# untitled.net
KiCad netlist of a schematic drawn in EAGLE
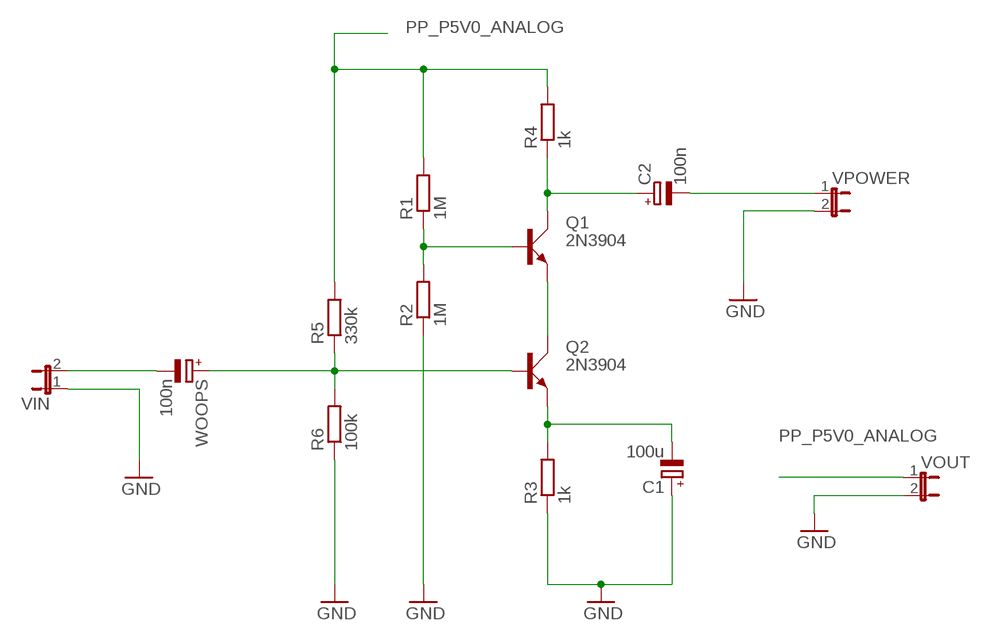
[diagram p0: schematic, sheet 1]

(export (version "E")
  (design (tool "Eeschema 10.0.6"))
  (components
    (comp (ref "C1")
      (value "100u")
      (footprint "eagle-import:E5-10,5")
      (libsource (lib "eagle-import") (part "CPOL-EUE5-10.5"))
    )
    (comp (ref "C2")
      (value "100n")
      (footprint "eagle-import:EB25D")
      (libsource (lib "eagle-import") (part "CPOL-EUE10-25"))
    )
    (comp (ref "Q1")
      (value "2N3904")
      (footprint "eagle-import:TO92D")
      (libsource (lib "eagle-import") (part "2N3904"))
    )
    (comp (ref "Q2")
      (value "2N3904")
      (footprint "eagle-import:TO92D")
      (libsource (lib "eagle-import") (part "2N3904"))
    )
    (comp (ref "R1")
      (value "1M")
      (footprint "eagle-import:0207_10")
      (libsource (lib "eagle-import") (part "R-EU_0207/10"))
    )
    (comp (ref "R2")
      (value "1M")
      (footprint "eagle-import:0207_10")
      (libsource (lib "eagle-import") (part "R-EU_0207/10"))
    )
    (comp (ref "R3")
      (value "1k")
      (footprint "eagle-import:0207_10")
      (libsource (lib "eagle-import") (part "R-EU_0207/10"))
    )
    (comp (ref "R4")
      (value "1k")
      (footprint "eagle-import:0207_10")
      (libsource (lib "eagle-import") (part "R-EU_0207/10"))
    )
    (comp (ref "R5")
      (value "330k")
      (footprint "eagle-import:0207_10")
      (libsource (lib "eagle-import") (part "R-EU_0207/10"))
    )
    (comp (ref "R6")
      (value "100k")
      (footprint "eagle-import:0207_10")
      (libsource (lib "eagle-import") (part "R-EU_0207/10"))
    )
    (comp (ref "VIN")
      (value "JP1E")
      (footprint "eagle-import:JP1")
      (libsource (lib "eagle-import") (part "JP1E"))
    )
    (comp (ref "VOUT")
      (value "JP1E")
      (footprint "eagle-import:JP1")
      (libsource (lib "eagle-import") (part "JP1E"))
    )
    (comp (ref "VPOWER")
      (value "JP1E")
      (footprint "eagle-import:JP1")
      (libsource (lib "eagle-import") (part "JP1E"))
    )
    (comp (ref "WOOPS")
      (value "100n")
      (footprint "eagle-import:E3,5-10")
      (libsource (lib "eagle-import") (part "resistor_CPOL-EUE3.5-10"))
    )
  )
  (nets
    (net (code "1") (name "/PP_P5V0_ANALOG") (class "Default")
      (node (ref "R1") (pin "2") (pinfunction "2_2") (pintype "passive"))
      (node (ref "R4") (pin "2") (pinfunction "2_2") (pintype "passive"))
      (node (ref "R5") (pin "2") (pinfunction "2_2") (pintype "passive"))
      (node (ref "VOUT") (pin "1") (pinfunction "1_1") (pintype "passive"))
    )
    (net (code "2") (name "GND") (class "Default")
      (node (ref "C1") (pin "+") (pinfunction "+_+") (pintype "passive"))
      (node (ref "R2") (pin "1") (pinfunction "1_1") (pintype "passive"))
      (node (ref "R3") (pin "1") (pinfunction "1_1") (pintype "passive"))
      (node (ref "R6") (pin "1") (pinfunction "1_1") (pintype "passive"))
      (node (ref "VIN") (pin "1") (pinfunction "1_1") (pintype "passive"))
      (node (ref "VOUT") (pin "2") (pinfunction "2_2") (pintype "passive"))
      (node (ref "VPOWER") (pin "2") (pinfunction "2_2") (pintype "passive"))
    )
    (net (code "3") (name "Net-(C1-Pad-)") (class "Default")
      (node (ref "C1") (pin "-") (pinfunction "-_-") (pintype "passive"))
      (node (ref "Q2") (pin "E") (pinfunction "E_E") (pintype "passive"))
      (node (ref "R3") (pin "2") (pinfunction "2_2") (pintype "passive"))
    )
    (net (code "4") (name "Net-(C2-Pad+)") (class "Default")
      (node (ref "C2") (pin "+") (pinfunction "+_+") (pintype "passive"))
      (node (ref "Q1") (pin "C") (pinfunction "C_C") (pintype "passive"))
      (node (ref "R4") (pin "1") (pinfunction "1_1") (pintype "passive"))
    )
    (net (code "5") (name "Net-(C2-Pad-)") (class "Default")
      (node (ref "C2") (pin "-") (pinfunction "-_-") (pintype "passive"))
      (node (ref "VPOWER") (pin "1") (pinfunction "1_1") (pintype "passive"))
    )
    (net (code "6") (name "Net-(Q1-PadB)") (class "Default")
      (node (ref "Q1") (pin "B") (pinfunction "B_B") (pintype "passive"))
      (node (ref "R1") (pin "1") (pinfunction "1_1") (pintype "passive"))
      (node (ref "R2") (pin "2") (pinfunction "2_2") (pintype "passive"))
    )
    (net (code "7") (name "Net-(Q1-PadE)") (class "Default")
      (node (ref "Q1") (pin "E") (pinfunction "E_E") (pintype "passive"))
      (node (ref "Q2") (pin "C") (pinfunction "C_C") (pintype "passive"))
    )
    (net (code "8") (name "Net-(Q2-PadB)") (class "Default")
      (node (ref "Q2") (pin "B") (pinfunction "B_B") (pintype "passive"))
      (node (ref "R5") (pin "1") (pinfunction "1_1") (pintype "passive"))
      (node (ref "R6") (pin "2") (pinfunction "2_2") (pintype "passive"))
      (node (ref "WOOPS") (pin "+") (pinfunction "+_+") (pintype "passive"))
    )
    (net (code "9") (name "Net-(VIN-Pad2)") (class "Default")
      (node (ref "VIN") (pin "2") (pinfunction "2_2") (pintype "passive"))
      (node (ref "WOOPS") (pin "-") (pinfunction "-_-") (pintype "passive"))
    )
  )
)
